# USBtoSPI.net
KiCad netlist of a schematic drawn in EAGLE
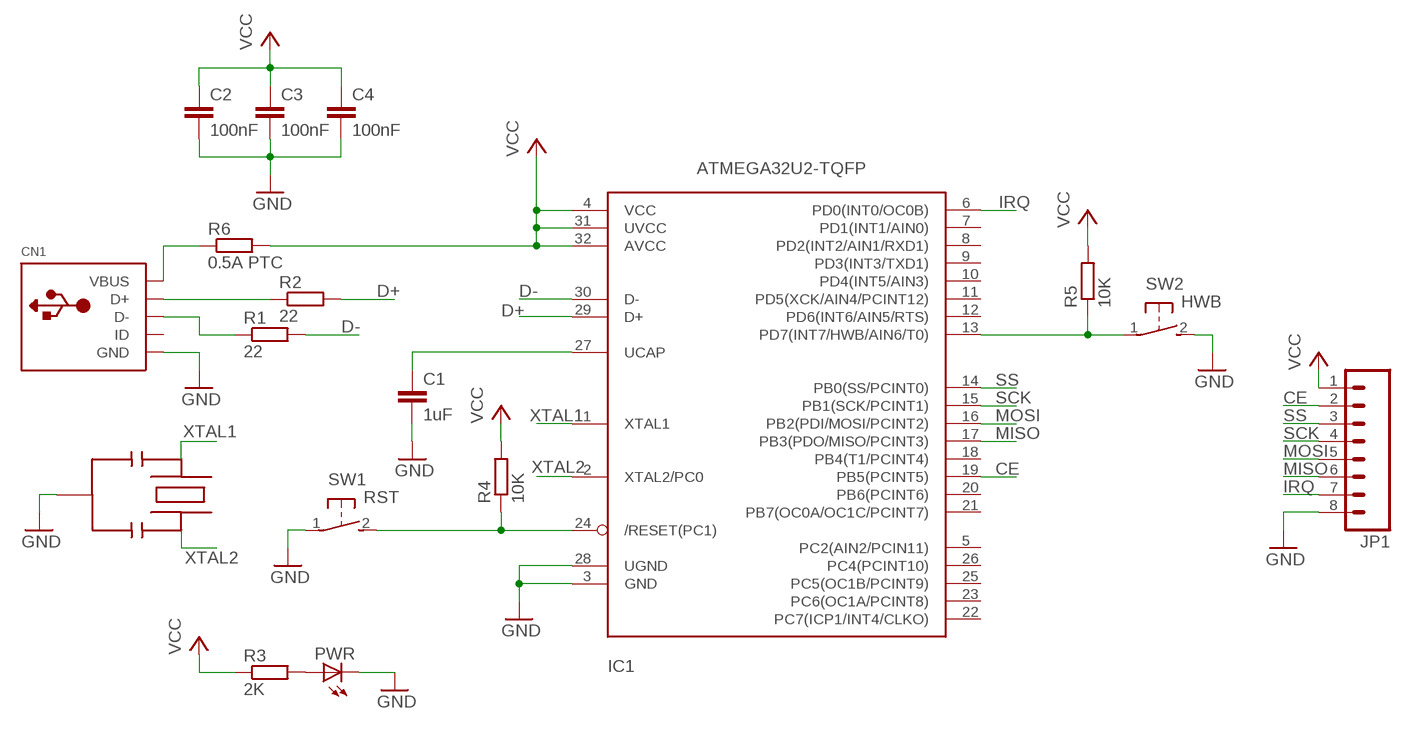
[diagram p0: schematic, sheet 1]

(export (version "E")
  (design (tool "Eeschema 10.0.6"))
  (components
    (comp (ref "C1")
      (value "1uF")
      (footprint "eagle-import:C0603")
      (libsource (lib "eagle-import") (part "C-EUC0603"))
    )
    (comp (ref "C2")
      (value "100nF")
      (footprint "eagle-import:C0603")
      (libsource (lib "eagle-import") (part "C-EUC0603"))
    )
    (comp (ref "C3")
      (value "100nF")
      (footprint "eagle-import:C0603")
      (libsource (lib "eagle-import") (part "C-EUC0603"))
    )
    (comp (ref "C4")
      (value "100nF")
      (footprint "eagle-import:C0603")
      (libsource (lib "eagle-import") (part "C-EUC0603"))
    )
    (comp (ref "CN1")
      (value "USBMINIB")
      (footprint "eagle-import:USB-MINIB")
      (libsource (lib "eagle-import") (part "USBMINIB"))
    )
    (comp (ref "IC1")
      (value "ATMEGA32U2-TQFP")
      (footprint "eagle-import:TQFP32-08")
      (libsource (lib "eagle-import") (part "ATMEGA32U2-TQFP"))
    )
    (comp (ref "JP1")
      (value "M081X08")
      (footprint "eagle-import:1X08")
      (libsource (lib "eagle-import") (part "M081X08"))
    )
    (comp (ref "PWR")
      (value "LEDCHIP-LED0603")
      (footprint "eagle-import:CHIP-LED0603")
      (libsource (lib "eagle-import") (part "LEDCHIP-LED0603"))
    )
    (comp (ref "R1")
      (value "22")
      (footprint "eagle-import:R0603")
      (libsource (lib "eagle-import") (part "R-EU_R0603"))
    )
    (comp (ref "R2")
      (value "22")
      (footprint "eagle-import:R0603")
      (libsource (lib "eagle-import") (part "R-EU_R0603"))
    )
    (comp (ref "R3")
      (value "2K")
      (footprint "eagle-import:R0603")
      (libsource (lib "eagle-import") (part "R-EU_R0603"))
    )
    (comp (ref "R4")
      (value "10K")
      (footprint "eagle-import:R0603")
      (libsource (lib "eagle-import") (part "R-EU_R0603"))
    )
    (comp (ref "R5")
      (value "10K")
      (footprint "eagle-import:R0603")
      (libsource (lib "eagle-import") (part "R-EU_R0603"))
    )
    (comp (ref "R6")
      (value "0.5A PTC")
      (footprint "eagle-import:R1210")
      (libsource (lib "eagle-import") (part "R-EU_R1210"))
    )
    (comp (ref "SW1")
      (value "RST")
      (footprint "eagle-import:SMD-TACT-3.9X2.9")
      (libsource (lib "eagle-import") (part "SMD-TACT-3.9X2.9"))
    )
    (comp (ref "SW2")
      (value "HWB")
      (footprint "eagle-import:SMD-TACT-3.9X2.9")
      (libsource (lib "eagle-import") (part "SMD-TACT-3.9X2.9"))
    )
    (comp (ref "U$1")
      (value "SMDRESONATORPBRC-H")
      (footprint "eagle-import:SMDRESONATOR")
      (libsource (lib "eagle-import") (part "SMDRESONATORPBRC-H"))
    )
  )
  (nets
    (net (code "1") (name "/CE") (class "Default")
      (node (ref "IC1") (pin "19") (pinfunction "PB5(PCINT5)_19") (pintype "bidirectional"))
      (node (ref "JP1") (pin "2") (pinfunction "2_2") (pintype "passive"))
    )
    (net (code "2") (name "/D+") (class "Default")
      (node (ref "IC1") (pin "29") (pinfunction "D+_29") (pintype "bidirectional"))
      (node (ref "R2") (pin "2") (pinfunction "2_2") (pintype "passive"))
    )
    (net (code "3") (name "/D-") (class "Default")
      (node (ref "IC1") (pin "30") (pinfunction "D-_30") (pintype "bidirectional"))
      (node (ref "R1") (pin "2") (pinfunction "2_2") (pintype "passive"))
    )
    (net (code "4") (name "/IRQ") (class "Default")
      (node (ref "IC1") (pin "6") (pinfunction "PD0(INT0/OC0B)_6") (pintype "bidirectional"))
      (node (ref "JP1") (pin "7") (pinfunction "7_7") (pintype "passive"))
    )
    (net (code "5") (name "/MISO") (class "Default")
      (node (ref "IC1") (pin "17") (pinfunction "PB3(PDO/MISO/PCINT3)_17") (pintype "bidirectional"))
      (node (ref "JP1") (pin "6") (pinfunction "6_6") (pintype "passive"))
    )
    (net (code "6") (name "/MOSI") (class "Default")
      (node (ref "IC1") (pin "16") (pinfunction "PB2(PDI/MOSI/PCINT2)_16") (pintype "bidirectional"))
      (node (ref "JP1") (pin "5") (pinfunction "5_5") (pintype "passive"))
    )
    (net (code "7") (name "/SCK") (class "Default")
      (node (ref "IC1") (pin "15") (pinfunction "PB1(SCK/PCINT1)_15") (pintype "bidirectional"))
      (node (ref "JP1") (pin "4") (pinfunction "4_4") (pintype "passive"))
    )
    (net (code "8") (name "/SS") (class "Default")
      (node (ref "IC1") (pin "14") (pinfunction "PB0(SS/PCINT0)_14") (pintype "bidirectional"))
      (node (ref "JP1") (pin "3") (pinfunction "3_3") (pintype "passive"))
    )
    (net (code "9") (name "/XTAL1") (class "Default")
      (node (ref "IC1") (pin "1") (pinfunction "XTAL1_1") (pintype "bidirectional"))
      (node (ref "U$1") (pin "P$2") (pinfunction "P$2_P$2") (pintype "input"))
    )
    (net (code "10") (name "/XTAL2") (class "Default")
      (node (ref "IC1") (pin "2") (pinfunction "XTAL2/PC0_2") (pintype "bidirectional"))
      (node (ref "U$1") (pin "P$3") (pinfunction "P$3_P$3") (pintype "input"))
    )
    (net (code "11") (name "GND") (class "Default")
      (node (ref "C1") (pin "2") (pinfunction "2_2") (pintype "passive"))
      (node (ref "C2") (pin "2") (pinfunction "2_2") (pintype "passive"))
      (node (ref "C3") (pin "2") (pinfunction "2_2") (pintype "passive"))
      (node (ref "C4") (pin "2") (pinfunction "2_2") (pintype "passive"))
      (node (ref "CN1") (pin "GND") (pinfunction "GND_GND") (pintype "power_in"))
      (node (ref "IC1") (pin "28") (pinfunction "UGND_28") (pintype "bidirectional"))
      (node (ref "IC1") (pin "3") (pinfunction "GND_3") (pintype "bidirectional"))
      (node (ref "JP1") (pin "8") (pinfunction "8_8") (pintype "passive"))
      (node (ref "PWR") (pin "C") (pinfunction "C_C") (pintype "passive"))
      (node (ref "SW1") (pin "1") (pinfunction "1_1") (pintype "passive"))
      (node (ref "SW2") (pin "2") (pinfunction "2_2") (pintype "passive"))
      (node (ref "U$1") (pin "P$1") (pinfunction "P$1_P$1") (pintype "input"))
    )
    (net (code "12") (name "Net-(CN1-PadD+)") (class "Default")
      (node (ref "CN1") (pin "D+") (pinfunction "D+_D+") (pintype "bidirectional"))
      (node (ref "R2") (pin "1") (pinfunction "1_1") (pintype "passive"))
    )
    (net (code "13") (name "Net-(CN1-PadD-)") (class "Default")
      (node (ref "CN1") (pin "D-") (pinfunction "D-_D-") (pintype "bidirectional"))
      (node (ref "R1") (pin "1") (pinfunction "1_1") (pintype "passive"))
    )
    (net (code "14") (name "Net-(CN1-PadVBUS)") (class "Default")
      (node (ref "CN1") (pin "VBUS") (pinfunction "VBUS_VBUS") (pintype "power_in"))
      (node (ref "R6") (pin "1") (pinfunction "1_1") (pintype "passive"))
    )
    (net (code "15") (name "Net-(IC1-PD7(INT7{slash}HWB{slash}AIN6{slash}T0))") (class "Default")
      (node (ref "IC1") (pin "13") (pinfunction "PD7(INT7/HWB/AIN6/T0)_13") (pintype "bidirectional"))
      (node (ref "R5") (pin "1") (pinfunction "1_1") (pintype "passive"))
      (node (ref "SW2") (pin "1") (pinfunction "1_1") (pintype "passive"))
    )
    (net (code "16") (name "Net-(IC1-UCAP)") (class "Default")
      (node (ref "C1") (pin "1") (pinfunction "1_1") (pintype "passive"))
      (node (ref "IC1") (pin "27") (pinfunction "UCAP_27") (pintype "bidirectional"))
    )
    (net (code "17") (name "Net-(IC1-{slash}RESET(PC1))") (class "Default")
      (node (ref "IC1") (pin "24") (pinfunction "/RESET(PC1)_24") (pintype "bidirectional"))
      (node (ref "R4") (pin "1") (pinfunction "1_1") (pintype "passive"))
      (node (ref "SW1") (pin "2") (pinfunction "2_2") (pintype "passive"))
    )
    (net (code "18") (name "Net-(PWR-PadA)") (class "Default")
      (node (ref "PWR") (pin "A") (pinfunction "A_A") (pintype "passive"))
      (node (ref "R3") (pin "2") (pinfunction "2_2") (pintype "passive"))
    )
    (net (code "19") (name "VCC") (class "Default")
      (node (ref "C2") (pin "1") (pinfunction "1_1") (pintype "passive"))
      (node (ref "C3") (pin "1") (pinfunction "1_1") (pintype "passive"))
      (node (ref "C4") (pin "1") (pinfunction "1_1") (pintype "passive"))
      (node (ref "IC1") (pin "31") (pinfunction "UVCC_31") (pintype "bidirectional"))
      (node (ref "IC1") (pin "32") (pinfunction "AVCC_32") (pintype "bidirectional"))
      (node (ref "IC1") (pin "4") (pinfunction "VCC_4") (pintype "bidirectional"))
      (node (ref "JP1") (pin "1") (pinfunction "1_1") (pintype "passive"))
      (node (ref "R3") (pin "1") (pinfunction "1_1") (pintype "passive"))
      (node (ref "R4") (pin "2") (pinfunction "2_2") (pintype "passive"))
      (node (ref "R5") (pin "2") (pinfunction "2_2") (pintype "passive"))
      (node (ref "R6") (pin "2") (pinfunction "2_2") (pintype "passive"))
    )
    (net (code "20") (name "unconnected-(CN1-PadID)") (class "Default")
      (node (ref "CN1") (pin "ID") (pinfunction "ID_ID") (pintype "bidirectional"))
    )
    (net (code "21") (name "unconnected-(IC1-PB4(T1{slash}PCINT4)-Pad18)") (class "Default")
      (node (ref "IC1") (pin "18") (pinfunction "PB4(T1/PCINT4)_18") (pintype "bidirectional"))
    )
    (net (code "22") (name "unconnected-(IC1-PB6(PCINT6)-Pad20)") (class "Default")
      (node (ref "IC1") (pin "20") (pinfunction "PB6(PCINT6)_20") (pintype "bidirectional"))
    )
    (net (code "23") (name "unconnected-(IC1-PB7(OC0A{slash}OC1C{slash}PCINT7)-Pad21)") (class "Default")
      (node (ref "IC1") (pin "21") (pinfunction "PB7(OC0A/OC1C/PCINT7)_21") (pintype "bidirectional"))
    )
    (net (code "24") (name "unconnected-(IC1-PC2(AIN2{slash}PCIN11)-Pad5)") (class "Default")
      (node (ref "IC1") (pin "5") (pinfunction "PC2(AIN2/PCIN11)_5") (pintype "bidirectional"))
    )
    (net (code "25") (name "unconnected-(IC1-PC4(PCINT10)-Pad26)") (class "Default")
      (node (ref "IC1") (pin "26") (pinfunction "PC4(PCINT10)_26") (pintype "bidirectional"))
    )
    (net (code "26") (name "unconnected-(IC1-PC5(OC1B{slash}PCINT9)-Pad25)") (class "Default")
      (node (ref "IC1") (pin "25") (pinfunction "PC5(OC1B/PCINT9)_25") (pintype "bidirectional"))
    )
    (net (code "27") (name "unconnected-(IC1-PC6(OC1A{slash}PCINT8)-Pad23)") (class "Default")
      (node (ref "IC1") (pin "23") (pinfunction "PC6(OC1A/PCINT8)_23") (pintype "bidirectional"))
    )
    (net (code "28") (name "unconnected-(IC1-PC7(ICP1{slash}INT4{slash}CLKO)-Pad22)") (class "Default")
      (node (ref "IC1") (pin "22") (pinfunction "PC7(ICP1/INT4/CLKO)_22") (pintype "bidirectional"))
    )
    (net (code "29") (name "unconnected-(IC1-PD1(INT1{slash}AIN0)-Pad7)") (class "Default")
      (node (ref "IC1") (pin "7") (pinfunction "PD1(INT1/AIN0)_7") (pintype "bidirectional"))
    )
    (net (code "30") (name "unconnected-(IC1-PD2(INT2{slash}AIN1{slash}RXD1)-Pad8)") (class "Default")
      (node (ref "IC1") (pin "8") (pinfunction "PD2(INT2/AIN1/RXD1)_8") (pintype "bidirectional"))
    )
    (net (code "31") (name "unconnected-(IC1-PD3(INT3{slash}TXD1)-Pad9)") (class "Default")
      (node (ref "IC1") (pin "9") (pinfunction "PD3(INT3/TXD1)_9") (pintype "bidirectional"))
    )
    (net (code "32") (name "unconnected-(IC1-PD4(INT5{slash}AIN3)-Pad10)") (class "Default")
      (node (ref "IC1") (pin "10") (pinfunction "PD4(INT5/AIN3)_10") (pintype "bidirectional"))
    )
    (net (code "33") (name "unconnected-(IC1-PD5(XCK{slash}AIN4{slash}PCINT12)-Pad11)") (class "Default")
      (node (ref "IC1") (pin "11") (pinfunction "PD5(XCK/AIN4/PCINT12)_11") (pintype "bidirectional"))
    )
    (net (code "34") (name "unconnected-(IC1-PD6(INT6{slash}AIN5{slash}RTS)-Pad12)") (class "Default")
      (node (ref "IC1") (pin "12") (pinfunction "PD6(INT6/AIN5/RTS)_12") (pintype "bidirectional"))
    )
  )
)
